# HARE_-_Master_Schematic_v1_0.net
KiCad netlist of a schematic drawn in EAGLE
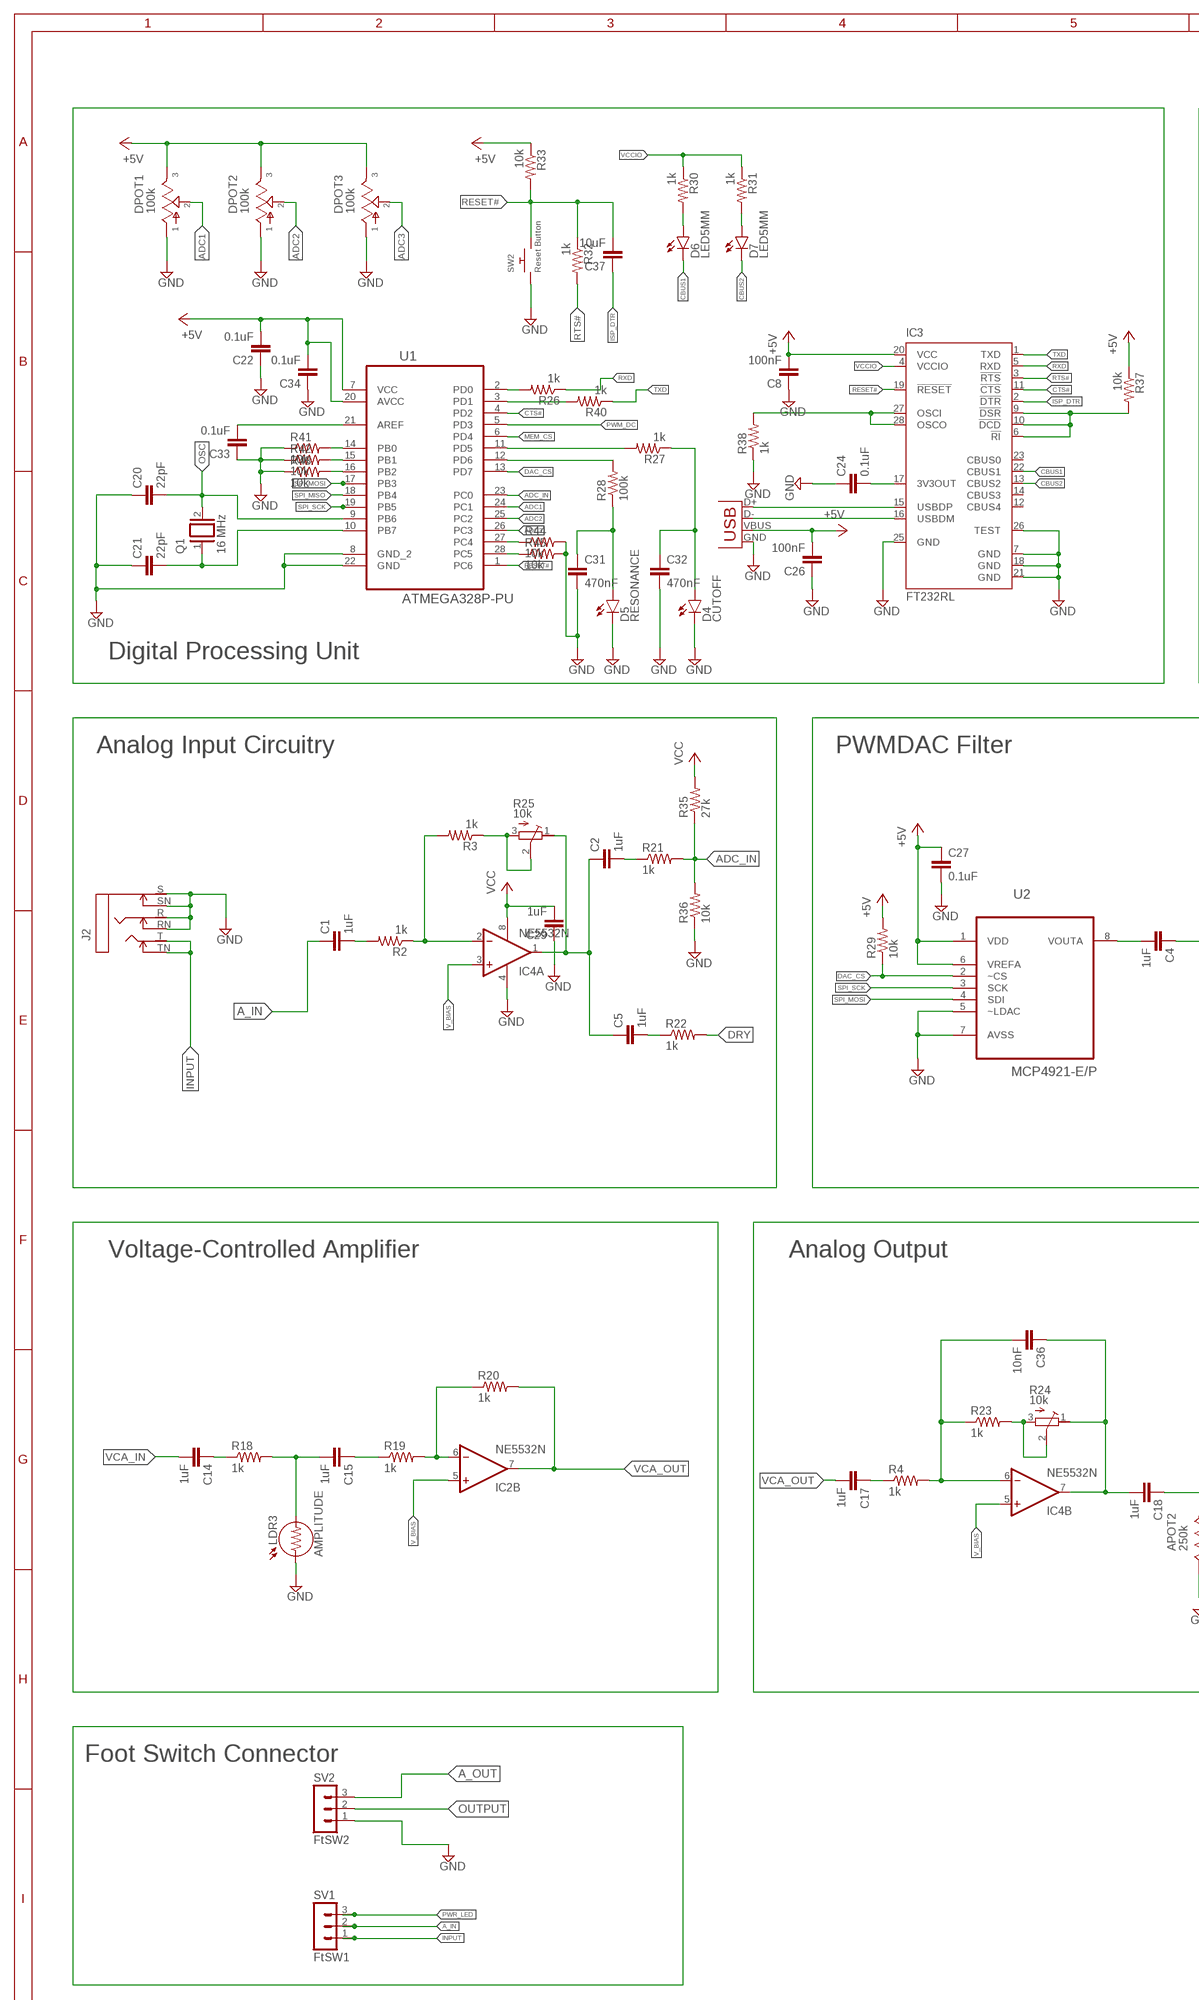
[diagram p0: schematic, sheet 1, part 1 of 2]
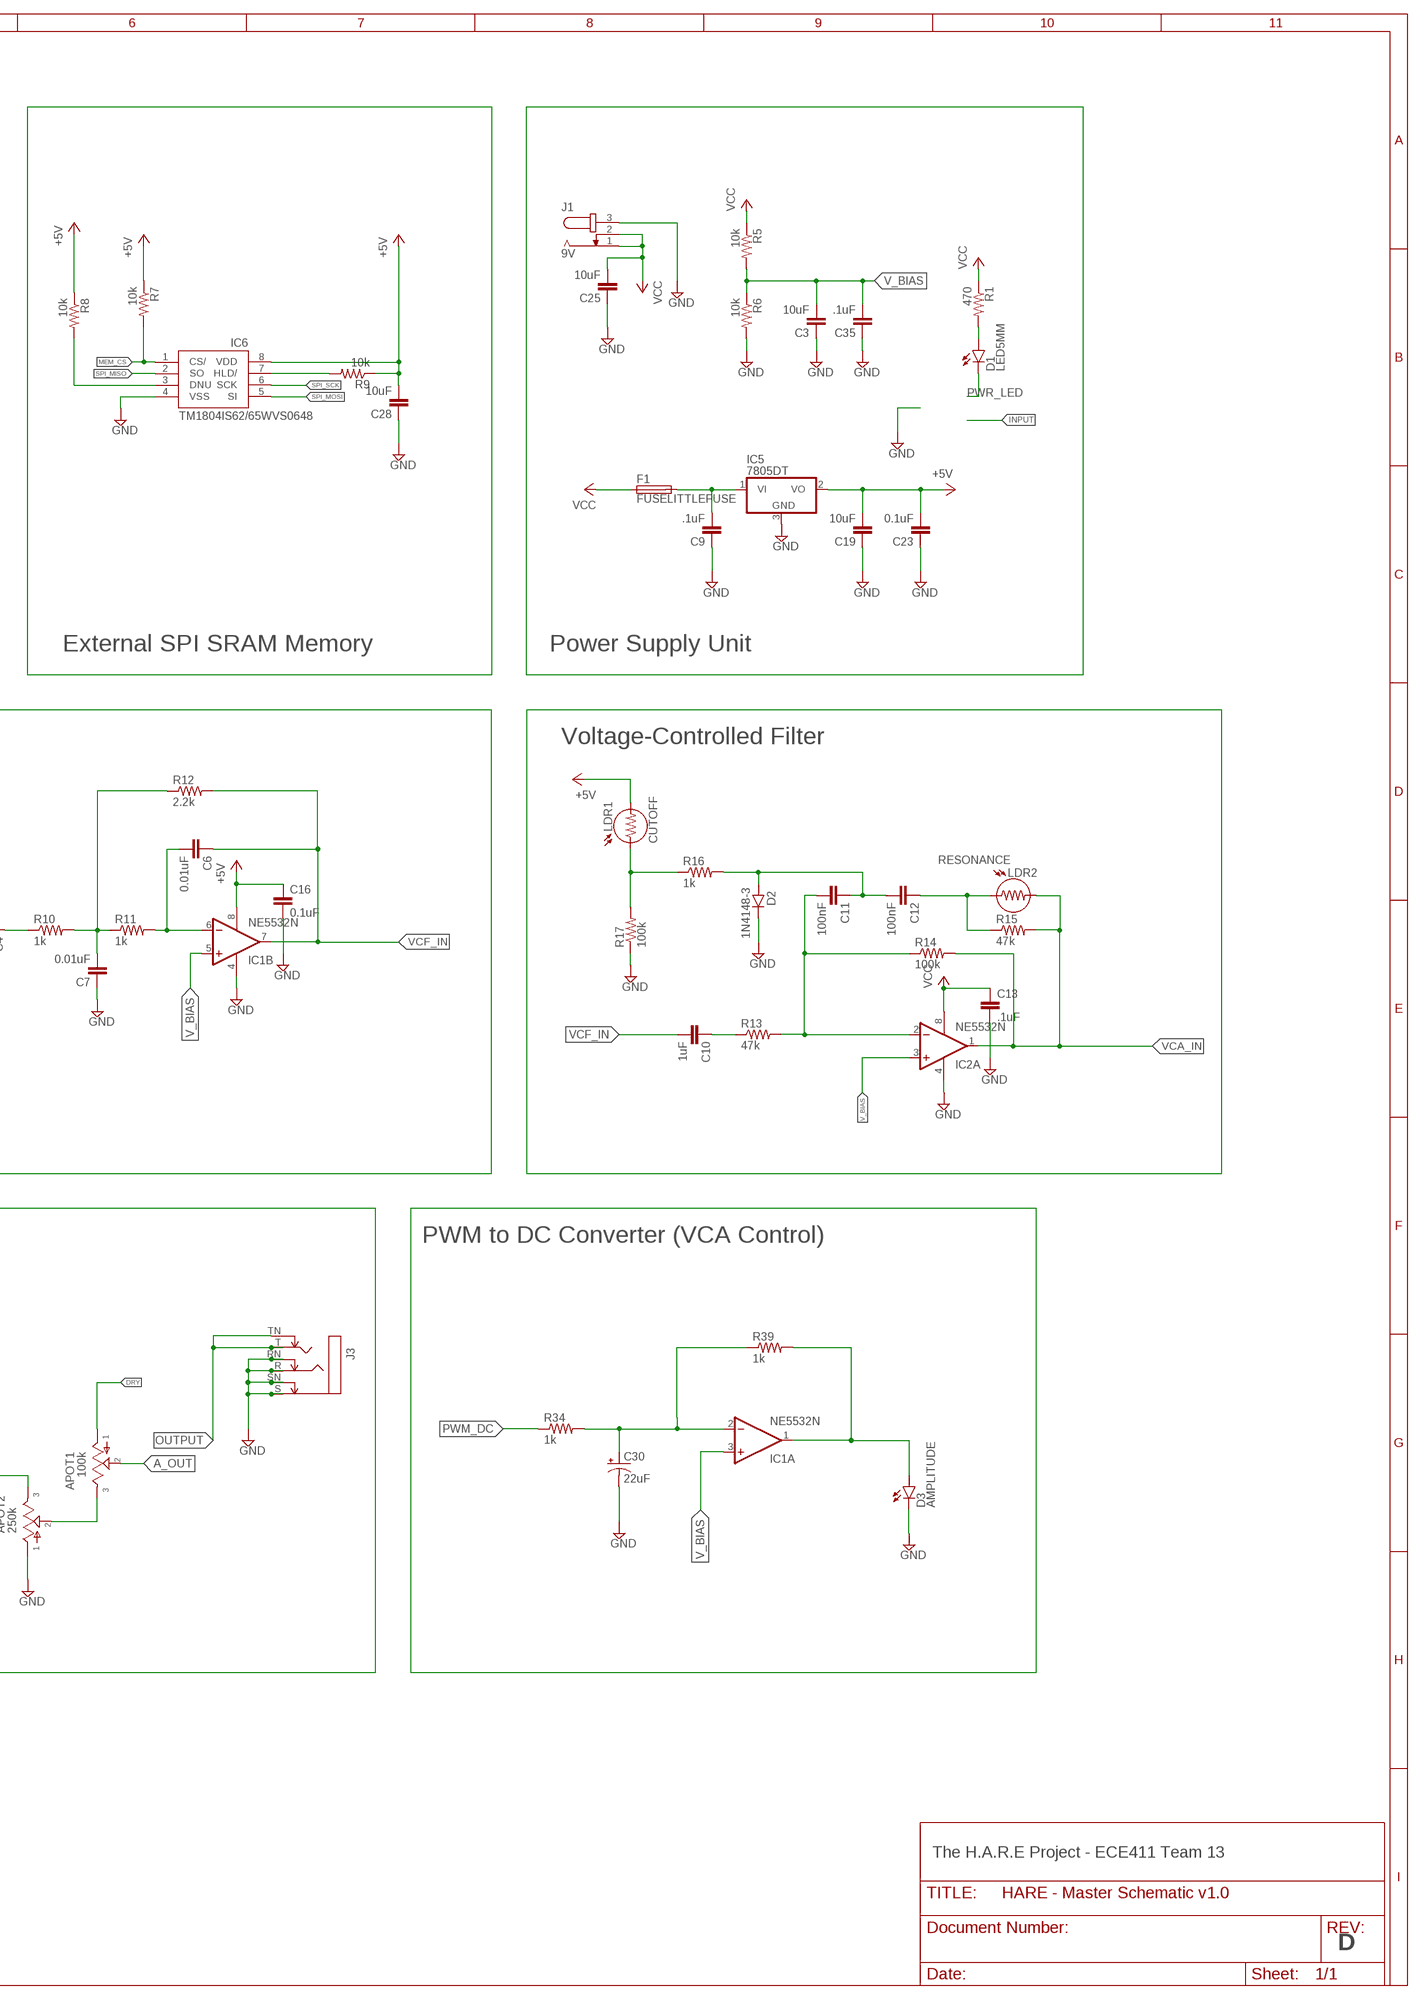
[diagram p1: schematic, sheet 1, part 2 of 2]

(export (version "E")
  (design (tool "Eeschema 10.0.6"))
  (components
    (comp (ref "APOT1")
      (value "100k")
      (footprint "eagle-import:16MM-SQUARE")
      (libsource (lib "eagle-import") (part "POTS"))
    )
    (comp (ref "APOT2")
      (value "250k")
      (footprint "eagle-import:16MM-SQUARE")
      (libsource (lib "eagle-import") (part "POTS"))
    )
    (comp (ref "C1")
      (value "1uF")
      (footprint "eagle-import:C0805K")
      (libsource (lib "eagle-import") (part "C-EUC0805K"))
    )
    (comp (ref "C2")
      (value "1uF")
      (footprint "eagle-import:C0805K")
      (libsource (lib "eagle-import") (part "C-EUC0805K"))
    )
    (comp (ref "C3")
      (value "10uF")
      (footprint "eagle-import:C0805K")
      (libsource (lib "eagle-import") (part "C-EUC0805K"))
    )
    (comp (ref "C4")
      (value "1uF")
      (footprint "eagle-import:C0805K")
      (libsource (lib "eagle-import") (part "C-EUC0805K"))
    )
    (comp (ref "C5")
      (value "1uF")
      (footprint "eagle-import:C0805K")
      (libsource (lib "eagle-import") (part "C-EUC0805K"))
    )
    (comp (ref "C6")
      (value "0.01uF")
      (footprint "eagle-import:C0805K")
      (libsource (lib "eagle-import") (part "C-EUC0805K"))
    )
    (comp (ref "C7")
      (value "0.01uF")
      (footprint "eagle-import:C0805K")
      (libsource (lib "eagle-import") (part "C-EUC0805K"))
    )
    (comp (ref "C8")
      (value "100nF")
      (footprint "eagle-import:C0805K")
      (libsource (lib "eagle-import") (part "C-EUC0805K"))
    )
    (comp (ref "C9")
      (value ".1uF")
      (footprint "eagle-import:C0805K")
      (libsource (lib "eagle-import") (part "C-EUC0805K"))
    )
    (comp (ref "C10")
      (value "1uF")
      (footprint "eagle-import:C0805K")
      (libsource (lib "eagle-import") (part "C-EUC0805K"))
    )
    (comp (ref "C11")
      (value "100nF")
      (footprint "eagle-import:C0805K")
      (libsource (lib "eagle-import") (part "C-EUC0805K"))
    )
    (comp (ref "C12")
      (value "100nF")
      (footprint "eagle-import:C0805K")
      (libsource (lib "eagle-import") (part "C-EUC0805K"))
    )
    (comp (ref "C13")
      (value ".1uF")
      (footprint "eagle-import:C0805K")
      (libsource (lib "eagle-import") (part "C-EUC0805K"))
    )
    (comp (ref "C14")
      (value "1uF")
      (footprint "eagle-import:C0805K")
      (libsource (lib "eagle-import") (part "C-EUC0805K"))
    )
    (comp (ref "C15")
      (value "1uF")
      (footprint "eagle-import:C0805K")
      (libsource (lib "eagle-import") (part "C-EUC0805K"))
    )
    (comp (ref "C16")
      (value "0.1uF")
      (footprint "eagle-import:C0805K")
      (libsource (lib "eagle-import") (part "C-EUC0805K"))
    )
    (comp (ref "C17")
      (value "1uF")
      (footprint "eagle-import:C0805K")
      (libsource (lib "eagle-import") (part "C-EUC0805K"))
    )
    (comp (ref "C18")
      (value "1uF")
      (footprint "eagle-import:C0805K")
      (libsource (lib "eagle-import") (part "C-EUC0805K"))
    )
    (comp (ref "C19")
      (value "10uF")
      (footprint "eagle-import:C0805K")
      (libsource (lib "eagle-import") (part "C-EUC0805K"))
    )
    (comp (ref "C20")
      (value "22pF")
      (footprint "eagle-import:C0805K")
      (libsource (lib "eagle-import") (part "C-EUC0805K"))
    )
    (comp (ref "C21")
      (value "22pF")
      (footprint "eagle-import:C0805K")
      (libsource (lib "eagle-import") (part "C-EUC0805K"))
    )
    (comp (ref "C22")
      (value "0.1uF")
      (footprint "eagle-import:C0805K")
      (libsource (lib "eagle-import") (part "C-EUC0805K"))
    )
    (comp (ref "C23")
      (value "0.1uF")
      (footprint "eagle-import:C0805K")
      (libsource (lib "eagle-import") (part "C-EUC0805K"))
    )
    (comp (ref "C24")
      (value "0.1uF")
      (footprint "eagle-import:C0805K")
      (libsource (lib "eagle-import") (part "C-EUC0805K"))
    )
    (comp (ref "C25")
      (value "10uF")
      (footprint "eagle-import:C0805K")
      (libsource (lib "eagle-import") (part "C-EUC0805K"))
    )
    (comp (ref "C26")
      (value "100nF")
      (footprint "eagle-import:C0805K")
      (libsource (lib "eagle-import") (part "C-EUC0805K"))
    )
    (comp (ref "C27")
      (value "0.1uF")
      (footprint "eagle-import:C0805K")
      (libsource (lib "eagle-import") (part "C-EUC0805K"))
    )
    (comp (ref "C28")
      (value "10uF")
      (footprint "eagle-import:C0805K")
      (libsource (lib "eagle-import") (part "C-EUC0805K"))
    )
    (comp (ref "C29")
      (value "1uF")
      (footprint "eagle-import:C0805K")
      (libsource (lib "eagle-import") (part "C-EUC0805K"))
    )
    (comp (ref "C30")
      (value "22uF")
      (footprint "eagle-import:050_020_1")
      (libsource (lib "eagle-import") (part "0501"))
    )
    (comp (ref "C31")
      (value "470nF")
      (footprint "eagle-import:072X035")
      (libsource (lib "eagle-import") (part "072X0352"))
    )
    (comp (ref "C32")
      (value "470nF")
      (footprint "eagle-import:072X035")
      (libsource (lib "eagle-import") (part "072X0352"))
    )
    (comp (ref "C33")
      (value "0.1uF")
      (footprint "eagle-import:C0805K")
      (libsource (lib "eagle-import") (part "C-EUC0805K"))
    )
    (comp (ref "C34")
      (value "0.1uF")
      (footprint "eagle-import:C0805K")
      (libsource (lib "eagle-import") (part "C-EUC0805K"))
    )
    (comp (ref "C35")
      (value ".1uF")
      (footprint "eagle-import:C0805K")
      (libsource (lib "eagle-import") (part "C-EUC0805K"))
    )
    (comp (ref "C36")
      (value "10nF")
      (footprint "eagle-import:C0805K")
      (libsource (lib "eagle-import") (part "C-EUC0805K"))
    )
    (comp (ref "C37")
      (value "10uF")
      (footprint "eagle-import:C0805K")
      (libsource (lib "eagle-import") (part "C-EUC0805K"))
    )
    (comp (ref "D1")
      (value "LED5MM")
      (footprint "eagle-import:LED5MM")
      (libsource (lib "eagle-import") (part "LED5MM"))
    )
    (comp (ref "D2")
      (value "1N4148-3")
      (footprint "eagle-import:DO35-3")
      (libsource (lib "eagle-import") (part "1N4148-3"))
    )
    (comp (ref "D3")
      (value "AMPLITUDE")
      (footprint "eagle-import:LED5MM")
      (libsource (lib "eagle-import") (part "LED5MM"))
    )
    (comp (ref "D4")
      (value "CUTOFF")
      (footprint "eagle-import:LED5MM")
      (libsource (lib "eagle-import") (part "LED5MM"))
    )
    (comp (ref "D5")
      (value "RESONANCE")
      (footprint "eagle-import:LED5MM")
      (libsource (lib "eagle-import") (part "LED5MM"))
    )
    (comp (ref "D6")
      (value "LED5MM")
      (footprint "eagle-import:LED5MM")
      (libsource (lib "eagle-import") (part "LED5MM"))
    )
    (comp (ref "D7")
      (value "LED5MM")
      (footprint "eagle-import:LED5MM")
      (libsource (lib "eagle-import") (part "LED5MM"))
    )
    (comp (ref "DPOT1")
      (value "100k")
      (footprint "eagle-import:16MM-SQUARE")
      (libsource (lib "eagle-import") (part "POTS"))
    )
    (comp (ref "DPOT2")
      (value "100k")
      (footprint "eagle-import:16MM-SQUARE")
      (libsource (lib "eagle-import") (part "POTS"))
    )
    (comp (ref "DPOT3")
      (value "100k")
      (footprint "eagle-import:16MM-SQUARE")
      (libsource (lib "eagle-import") (part "POTS"))
    )
    (comp (ref "F1")
      (value "FUSELITTLEFUSE")
      (footprint "eagle-import:LITTLEFUSE")
      (libsource (lib "eagle-import") (part "FUSELITTLEFUSE"))
    )
    (comp (ref "IC1")
      (value "NE5532N")
      (footprint "eagle-import:DIL08")
      (libsource (lib "eagle-import") (part "NE5532N"))
    )
    (comp (ref "IC2")
      (value "NE5532N")
      (footprint "eagle-import:DIL08")
      (libsource (lib "eagle-import") (part "NE5532N"))
    )
    (comp (ref "IC3")
      (value "FT232RL")
      (footprint "eagle-import:SSOP28")
      (libsource (lib "eagle-import") (part "FT232RL"))
    )
    (comp (ref "IC4")
      (value "NE5532N")
      (footprint "eagle-import:DIL08")
      (libsource (lib "eagle-import") (part "NE5532N"))
    )
    (comp (ref "IC5")
      (value "7805DT")
      (footprint "eagle-import:TO252")
      (libsource (lib "eagle-import") (part "78DT05"))
    )
    (comp (ref "IC6")
      (value "TM1804IS62/65WVS0648")
      (footprint "eagle-import:SO08")
      (libsource (lib "eagle-import") (part "TM1804IS62/65WVS0648"))
    )
    (comp (ref "J1")
      (value "9V")
      (footprint "eagle-import:SPC4078")
      (libsource (lib "eagle-import") (part "JACK-PLUG1"))
    )
    (comp (ref "J2")
      (value "STEREOSW")
      (footprint "eagle-import:NMJ6HCD2")
      (libsource (lib "eagle-import") (part "STEREOSW"))
    )
    (comp (ref "J3")
      (value "STEREOSW")
      (footprint "eagle-import:NMJ6HCD2")
      (libsource (lib "eagle-import") (part "STEREOSW"))
    )
    (comp (ref "LDR1")
      (value "CUTOFF")
      (footprint "eagle-import:LDR338-54C")
      (libsource (lib "eagle-import") (part "LDR5MM"))
    )
    (comp (ref "LDR2")
      (value "RESONANCE")
      (footprint "eagle-import:LDR338-54C")
      (libsource (lib "eagle-import") (part "LDR5MM"))
    )
    (comp (ref "LDR3")
      (value "AMPLITUDE")
      (footprint "eagle-import:LDR338-54C")
      (libsource (lib "eagle-import") (part "LDR5MM"))
    )
    (comp (ref "Q1")
      (value "16 MHz")
      (footprint "eagle-import:QS")
      (libsource (lib "eagle-import") (part "XTAL/S"))
    )
    (comp (ref "R1")
      (value "470")
      (footprint "eagle-import:M0805")
      (libsource (lib "eagle-import") (part "R-US_M0805"))
    )
    (comp (ref "R2")
      (value "1k")
      (footprint "eagle-import:R0805")
      (libsource (lib "eagle-import") (part "resistor_348_R-US_R0805"))
    )
    (comp (ref "R3")
      (value "1k")
      (footprint "eagle-import:R0805")
      (libsource (lib "eagle-import") (part "resistor_348_R-US_R0805"))
    )
    (comp (ref "R4")
      (value "1k")
      (footprint "eagle-import:R0805")
      (libsource (lib "eagle-import") (part "resistor_348_R-US_R0805"))
    )
    (comp (ref "R5")
      (value "10k")
      (footprint "eagle-import:M0805")
      (libsource (lib "eagle-import") (part "R-US_M0805"))
    )
    (comp (ref "R6")
      (value "10k")
      (footprint "eagle-import:M0805")
      (libsource (lib "eagle-import") (part "R-US_M0805"))
    )
    (comp (ref "R7")
      (value "10k")
      (footprint "eagle-import:M0805")
      (libsource (lib "eagle-import") (part "R-US_M0805"))
    )
    (comp (ref "R8")
      (value "10k")
      (footprint "eagle-import:M0805")
      (libsource (lib "eagle-import") (part "R-US_M0805"))
    )
    (comp (ref "R9")
      (value "10k")
      (footprint "eagle-import:M0805")
      (libsource (lib "eagle-import") (part "R-US_M0805"))
    )
    (comp (ref "R10")
      (value "1k")
      (footprint "eagle-import:R0805")
      (libsource (lib "eagle-import") (part "resistor_348_R-US_R0805"))
    )
    (comp (ref "R11")
      (value "1k")
      (footprint "eagle-import:R0805")
      (libsource (lib "eagle-import") (part "resistor_348_R-US_R0805"))
    )
    (comp (ref "R12")
      (value "2.2k")
      (footprint "eagle-import:R0805")
      (libsource (lib "eagle-import") (part "resistor_348_R-US_R0805"))
    )
    (comp (ref "R13")
      (value "47k")
      (footprint "eagle-import:R0805")
      (libsource (lib "eagle-import") (part "resistor_348_R-US_R0805"))
    )
    (comp (ref "R14")
      (value "100k")
      (footprint "eagle-import:R0805")
      (libsource (lib "eagle-import") (part "resistor_348_R-US_R0805"))
    )
    (comp (ref "R15")
      (value "47k")
      (footprint "eagle-import:R0805")
      (libsource (lib "eagle-import") (part "resistor_348_R-US_R0805"))
    )
    (comp (ref "R16")
      (value "1k")
      (footprint "eagle-import:R0805")
      (libsource (lib "eagle-import") (part "resistor_348_R-US_R0805"))
    )
    (comp (ref "R17")
      (value "100k")
      (footprint "eagle-import:R0805")
      (libsource (lib "eagle-import") (part "resistor_348_R-US_R0805"))
    )
    (comp (ref "R18")
      (value "1k")
      (footprint "eagle-import:R0805")
      (libsource (lib "eagle-import") (part "resistor_348_R-US_R0805"))
    )
    (comp (ref "R19")
      (value "1k")
      (footprint "eagle-import:R0805")
      (libsource (lib "eagle-import") (part "resistor_348_R-US_R0805"))
    )
    (comp (ref "R20")
      (value "1k")
      (footprint "eagle-import:R0805")
      (libsource (lib "eagle-import") (part "resistor_348_R-US_R0805"))
    )
    (comp (ref "R21")
      (value "1k")
      (footprint "eagle-import:R0805")
      (libsource (lib "eagle-import") (part "resistor_348_R-US_R0805"))
    )
    (comp (ref "R22")
      (value "1k")
      (footprint "eagle-import:R0805")
      (libsource (lib "eagle-import") (part "resistor_348_R-US_R0805"))
    )
    (comp (ref "R23")
      (value "1k")
      (footprint "eagle-import:R0805")
      (libsource (lib "eagle-import") (part "resistor_348_R-US_R0805"))
    )
    (comp (ref "R24")
      (value "10k")
      (footprint "eagle-import:RTRIM3314G")
      (libsource (lib "eagle-import") (part "R-TRIMM3314G"))
    )
    (comp (ref "R25")
      (value "10k")
      (footprint "eagle-import:RTRIM3314G")
      (libsource (lib "eagle-import") (part "R-TRIMM3314G"))
    )
    (comp (ref "R26")
      (value "1k")
      (footprint "eagle-import:R0805")
      (libsource (lib "eagle-import") (part "resistor_348_R-US_R0805"))
    )
    (comp (ref "R27")
      (value "1k")
      (footprint "eagle-import:R0805")
      (libsource (lib "eagle-import") (part "resistor_348_R-US_R0805"))
    )
    (comp (ref "R28")
      (value "100k")
      (footprint "eagle-import:R0805")
      (libsource (lib "eagle-import") (part "resistor_348_R-US_R0805"))
    )
    (comp (ref "R29")
      (value "10k")
      (footprint "eagle-import:R0805")
      (libsource (lib "eagle-import") (part "resistor_348_R-US_R0805"))
    )
    (comp (ref "R30")
      (value "1k")
      (footprint "eagle-import:R0805")
      (libsource (lib "eagle-import") (part "resistor_348_R-US_R0805"))
    )
    (comp (ref "R31")
      (value "1k")
      (footprint "eagle-import:R0805")
      (libsource (lib "eagle-import") (part "resistor_348_R-US_R0805"))
    )
    (comp (ref "R32")
      (value "1k")
      (footprint "eagle-import:R0805")
      (libsource (lib "eagle-import") (part "resistor_348_R-US_R0805"))
    )
    (comp (ref "R33")
      (value "10k")
      (footprint "eagle-import:R0805")
      (libsource (lib "eagle-import") (part "resistor_348_R-US_R0805"))
    )
    (comp (ref "R34")
      (value "1k")
      (footprint "eagle-import:R0805")
      (libsource (lib "eagle-import") (part "resistor_348_R-US_R0805"))
    )
    (comp (ref "R35")
      (value "27k")
      (footprint "eagle-import:R0805")
      (libsource (lib "eagle-import") (part "resistor_348_R-US_R0805"))
    )
    (comp (ref "R36")
      (value "10k")
      (footprint "eagle-import:R0805")
      (libsource (lib "eagle-import") (part "resistor_348_R-US_R0805"))
    )
    (comp (ref "R37")
      (value "10k")
      (footprint "eagle-import:R0805")
      (libsource (lib "eagle-import") (part "resistor_348_R-US_R0805"))
    )
    (comp (ref "R38")
      (value "1k")
      (footprint "eagle-import:R0805")
      (libsource (lib "eagle-import") (part "resistor_348_R-US_R0805"))
    )
    (comp (ref "R39")
      (value "1k")
      (footprint "eagle-import:R0805")
      (libsource (lib "eagle-import") (part "resistor_348_R-US_R0805"))
    )
    (comp (ref "R40")
      (value "1k")
      (footprint "eagle-import:R0805")
      (libsource (lib "eagle-import") (part "resistor_348_R-US_R0805"))
    )
    (comp (ref "R41")
      (value "10k")
      (footprint "eagle-import:R0805")
      (libsource (lib "eagle-import") (part "resistor_348_R-US_R0805"))
    )
    (comp (ref "R42")
      (value "10k")
      (footprint "eagle-import:R0805")
      (libsource (lib "eagle-import") (part "resistor_348_R-US_R0805"))
    )
    (comp (ref "R43")
      (value "10k")
      (footprint "eagle-import:R0805")
      (libsource (lib "eagle-import") (part "resistor_348_R-US_R0805"))
    )
    (comp (ref "R44")
      (value "10k")
      (footprint "eagle-import:R0805")
      (libsource (lib "eagle-import") (part "resistor_348_R-US_R0805"))
    )
    (comp (ref "R45")
      (value "10k")
      (footprint "eagle-import:R0805")
      (libsource (lib "eagle-import") (part "resistor_348_R-US_R0805"))
    )
    (comp (ref "SV1")
      (value "FtSW1")
      (footprint "eagle-import:MA03-1")
      (libsource (lib "eagle-import") (part "MA03-1"))
    )
    (comp (ref "SV2")
      (value "FtSW2")
      (footprint "eagle-import:MA03-1")
      (libsource (lib "eagle-import") (part "MA03-1"))
    )
    (comp (ref "SW2")
      (value "Reset Button")
      (footprint "eagle-import:PUSHBUTTON_SMD_SJ")
      (libsource (lib "eagle-import") (part "SWITCH_PUSHBUTTONSOFTTOUCHSMD_SJ"))
    )
    (comp (ref "U1")
      (value "ATMEGA328P-PU")
      (footprint "eagle-import:DIP254P762X457-28")
      (libsource (lib "eagle-import") (part "ATMEGA328P-PU"))
    )
    (comp (ref "U2")
      (value "MCP4921-E/P")
      (footprint "eagle-import:DIP254P762X432-8")
      (fields (field (name "MF") "Microchip"))
      (libsource (lib "eagle-import") (part "MCP4921-E/P"))
    )
    (comp (ref "X2")
      (value "USB-B-H")
      (footprint "eagle-import:USB-B-H")
      (libsource (lib "eagle-import") (part "USB-B-H"))
    )
  )
  (nets
    (net (code "1") (name "+5V") (class "Default")
      (node (ref "C16") (pin "1") (pinfunction "1_1") (pintype "passive"))
      (node (ref "C19") (pin "2") (pinfunction "2_2") (pintype "passive"))
      (node (ref "C22") (pin "2") (pinfunction "2_2") (pintype "passive"))
      (node (ref "C23") (pin "2") (pinfunction "2_2") (pintype "passive"))
      (node (ref "C26") (pin "2") (pinfunction "2_2") (pintype "passive"))
      (node (ref "C27") (pin "1") (pinfunction "1_1") (pintype "passive"))
      (node (ref "C28") (pin "2") (pinfunction "2_2") (pintype "passive"))
      (node (ref "C34") (pin "2") (pinfunction "2_2") (pintype "passive"))
      (node (ref "C8") (pin "2") (pinfunction "2_2") (pintype "passive"))
      (node (ref "DPOT1") (pin "3") (pinfunction "3_3") (pintype "passive"))
      (node (ref "DPOT2") (pin "3") (pinfunction "3_3") (pintype "passive"))
      (node (ref "DPOT3") (pin "3") (pinfunction "3_3") (pintype "passive"))
      (node (ref "IC1") (pin "8") (pinfunction "V+_8") (pintype "power_in"))
      (node (ref "IC3") (pin "20") (pinfunction "VCC_20") (pintype "power_in"))
      (node (ref "IC5") (pin "2") (pinfunction "VO_2") (pintype "passive"))
      (node (ref "IC6") (pin "8") (pinfunction "VDD_8") (pintype "power_in"))
      (node (ref "LDR1") (pin "2") (pinfunction "2_2") (pintype "passive"))
      (node (ref "R29") (pin "2") (pinfunction "2_2") (pintype "passive"))
      (node (ref "R33") (pin "1") (pinfunction "1_1") (pintype "passive"))
      (node (ref "R37") (pin "1") (pinfunction "1_1") (pintype "passive"))
      (node (ref "R7") (pin "1") (pinfunction "1_1") (pintype "passive"))
      (node (ref "R8") (pin "1") (pinfunction "1_1") (pintype "passive"))
      (node (ref "R9") (pin "1") (pinfunction "1_1") (pintype "passive"))
      (node (ref "U1") (pin "20") (pinfunction "AVCC_20") (pintype "power_in"))
      (node (ref "U1") (pin "7") (pinfunction "VCC_7") (pintype "power_in"))
      (node (ref "U2") (pin "1") (pinfunction "VDD_1") (pintype "power_in"))
      (node (ref "U2") (pin "6") (pinfunction "VREFA_6") (pintype "input"))
      (node (ref "X2") (pin "VBUS") (pinfunction "VBUS_VBUS") (pintype "bidirectional"))
    )
    (net (code "2") (name "ADC1") (class "Default")
      (node (ref "DPOT1") (pin "2") (pinfunction "2_2") (pintype "passive"))
      (node (ref "U1") (pin "24") (pinfunction "PC1_24") (pintype "bidirectional"))
    )
    (net (code "3") (name "ADC2") (class "Default")
      (node (ref "DPOT2") (pin "2") (pinfunction "2_2") (pintype "passive"))
      (node (ref "U1") (pin "25") (pinfunction "PC2_25") (pintype "bidirectional"))
    )
    (net (code "4") (name "ADC3") (class "Default")
      (node (ref "DPOT3") (pin "2") (pinfunction "2_2") (pintype "passive"))
      (node (ref "U1") (pin "26") (pinfunction "PC3_26") (pintype "bidirectional"))
    )
    (net (code "5") (name "ADC_IN") (class "Default")
      (node (ref "R21") (pin "2") (pinfunction "2_2") (pintype "passive"))
      (node (ref "R35") (pin "1") (pinfunction "1_1") (pintype "passive"))
      (node (ref "R36") (pin "2") (pinfunction "2_2") (pintype "passive"))
      (node (ref "U1") (pin "23") (pinfunction "PC0_23") (pintype "bidirectional"))
    )
    (net (code "6") (name "A_IN") (class "Default")
      (node (ref "C1") (pin "1") (pinfunction "1_1") (pintype "passive"))
      (node (ref "SV1") (pin "2") (pinfunction "2_2") (pintype "passive"))
    )
    (net (code "7") (name "A_OUT") (class "Default")
      (node (ref "APOT1") (pin "2") (pinfunction "2_2") (pintype "passive"))
      (node (ref "SV2") (pin "3") (pinfunction "3_3") (pintype "passive"))
    )
    (net (code "8") (name "CBUS1") (class "Default")
      (node (ref "D6") (pin "K") (pinfunction "C_K") (pintype "passive"))
      (node (ref "IC3") (pin "22") (pinfunction "CBUS1_22") (pintype "bidirectional"))
    )
    (net (code "9") (name "CBUS2") (class "Default")
      (node (ref "D7") (pin "K") (pinfunction "C_K") (pintype "passive"))
      (node (ref "IC3") (pin "13") (pinfunction "CBUS2_13") (pintype "bidirectional"))
    )
    (net (code "10") (name "CTS#") (class "Default")
      (node (ref "IC3") (pin "11") (pinfunction "~{CTS}_11") (pintype "input"))
      (node (ref "U1") (pin "4") (pinfunction "PD2_4") (pintype "bidirectional"))
    )
    (net (code "11") (name "DAC_CS") (class "Default")
      (node (ref "R29") (pin "1") (pinfunction "1_1") (pintype "passive"))
      (node (ref "U1") (pin "13") (pinfunction "PD7_13") (pintype "bidirectional"))
      (node (ref "U2") (pin "2") (pinfunction "~{CS}_2") (pintype "input"))
    )
    (net (code "12") (name "DRY") (class "Default")
      (node (ref "APOT1") (pin "1") (pinfunction "1_1") (pintype "passive"))
      (node (ref "R22") (pin "2") (pinfunction "2_2") (pintype "passive"))
    )
    (net (code "13") (name "GND") (class "Default")
      (node (ref "APOT2") (pin "1") (pinfunction "1_1") (pintype "passive"))
      (node (ref "C13") (pin "2") (pinfunction "2_2") (pintype "passive"))
      (node (ref "C16") (pin "2") (pinfunction "2_2") (pintype "passive"))
      (node (ref "C19") (pin "1") (pinfunction "1_1") (pintype "passive"))
      (node (ref "C20") (pin "1") (pinfunction "1_1") (pintype "passive"))
      (node (ref "C21") (pin "1") (pinfunction "1_1") (pintype "passive"))
      (node (ref "C22") (pin "1") (pinfunction "1_1") (pintype "passive"))
      (node (ref "C23") (pin "1") (pinfunction "1_1") (pintype "passive"))
      (node (ref "C24") (pin "1") (pinfunction "1_1") (pintype "passive"))
      (node (ref "C25") (pin "1") (pinfunction "1_1") (pintype "passive"))
      (node (ref "C26") (pin "1") (pinfunction "1_1") (pintype "passive"))
      (node (ref "C27") (pin "2") (pinfunction "2_2") (pintype "passive"))
      (node (ref "C28") (pin "1") (pinfunction "1_1") (pintype "passive"))
      (node (ref "C29") (pin "1") (pinfunction "1_1") (pintype "passive"))
      (node (ref "C3") (pin "1") (pinfunction "1_1") (pintype "passive"))
      (node (ref "C30") (pin "-") (pinfunction "-_-") (pintype "passive"))
      (node (ref "C31") (pin "2") (pinfunction "2_2") (pintype "passive"))
      (node (ref "C32") (pin "2") (pinfunction "2_2") (pintype "passive"))
      (node (ref "C33") (pin "1") (pinfunction "1_1") (pintype "passive"))
      (node (ref "C34") (pin "1") (pinfunction "1_1") (pintype "passive"))
      (node (ref "C35") (pin "1") (pinfunction "1_1") (pintype "passive"))
      (node (ref "C7") (pin "1") (pinfunction "1_1") (pintype "passive"))
      (node (ref "C8") (pin "1") (pinfunction "1_1") (pintype "passive"))
      (node (ref "C9") (pin "1") (pinfunction "1_1") (pintype "passive"))
      (node (ref "D2") (pin "C") (pinfunction "C_C") (pintype "passive"))
      (node (ref "D3") (pin "K") (pinfunction "C_K") (pintype "passive"))
      (node (ref "D4") (pin "K") (pinfunction "C_K") (pintype "passive"))
      (node (ref "D5") (pin "K") (pinfunction "C_K") (pintype "passive"))
      (node (ref "DPOT1") (pin "1") (pinfunction "1_1") (pintype "passive"))
      (node (ref "DPOT2") (pin "1") (pinfunction "1_1") (pintype "passive"))
      (node (ref "DPOT3") (pin "1") (pinfunction "1_1") (pintype "passive"))
      (node (ref "IC1") (pin "4") (pinfunction "V-_4") (pintype "power_in"))
      (node (ref "IC2") (pin "4") (pinfunction "V-_4") (pintype "power_in"))
      (node (ref "IC3") (pin "18") (pinfunction "GND_18") (pintype "power_in"))
      (node (ref "IC3") (pin "21") (pinfunction "GND_21") (pintype "power_in"))
      (node (ref "IC3") (pin "25") (pinfunction "GND_25") (pintype "power_in"))
      (node (ref "IC3") (pin "26") (pinfunction "TEST_26") (pintype "input"))
      (node (ref "IC3") (pin "7") (pinfunction "GND_7") (pintype "power_in"))
      (node (ref "IC4") (pin "4") (pinfunction "V-_4") (pintype "power_in"))
      (node (ref "IC5") (pin "3") (pinfunction "GND_3") (pintype "passive"))
      (node (ref "IC6") (pin "4") (pinfunction "VSS_4") (pintype "power_in"))
      (node (ref "J1") (pin "3") (pinfunction "3_3") (pintype "passive"))
      (node (ref "J2") (pin "R") (pinfunction "R_R") (pintype "passive"))
      (node (ref "J2") (pin "RN") (pinfunction "RN_RN") (pintype "passive"))
      (node (ref "J2") (pin "S") (pinfunction "S_S") (pintype "passive"))
      (node (ref "J2") (pin "SN") (pinfunction "SN_SN") (pintype "passive"))
      (node (ref "J3") (pin "R") (pinfunction "R_R") (pintype "passive"))
      (node (ref "J3") (pin "RN") (pinfunction "RN_RN") (pintype "passive"))
      (node (ref "J3") (pin "S") (pinfunction "S_S") (pintype "passive"))
      (node (ref "J3") (pin "SN") (pinfunction "SN_SN") (pintype "passive"))
      (node (ref "LDR3") (pin "1") (pinfunction "1_1") (pintype "passive"))
      (node (ref "R17") (pin "1") (pinfunction "1_1") (pintype "passive"))
      (node (ref "R36") (pin "1") (pinfunction "1_1") (pintype "passive"))
      (node (ref "R38") (pin "1") (pinfunction "1_1") (pintype "passive"))
      (node (ref "R41") (pin "1") (pinfunction "1_1") (pintype "passive"))
      (node (ref "R42") (pin "1") (pinfunction "1_1") (pintype "passive"))
      (node (ref "R43") (pin "1") (pinfunction "1_1") (pintype "passive"))
      (node (ref "R44") (pin "2") (pinfunction "2_2") (pintype "passive"))
      (node (ref "R45") (pin "2") (pinfunction "2_2") (pintype "passive"))
      (node (ref "R6") (pin "2") (pinfunction "2_2") (pintype "passive"))
      (node (ref "SV2") (pin "1") (pinfunction "1_1") (pintype "passive"))
      (node (ref "SW2") (pin "P$1") (pinfunction "P$1_P$1") (pintype "passive"))
      (node (ref "U1") (pin "22") (pinfunction "GND_22") (pintype "passive"))
      (node (ref "U1") (pin "8") (pinfunction "GND_2_8") (pintype "passive"))
      (node (ref "U2") (pin "5") (pinfunction "~{LDAC}_5") (pintype "input"))
      (node (ref "U2") (pin "7") (pinfunction "AVSS_7") (pintype "passive"))
      (node (ref "X2") (pin "GND") (pinfunction "GND_GND") (pintype "bidirectional"))
    )
    (net (code "14") (name "INPUT") (class "Default")
      (node (ref "J2") (pin "T") (pinfunction "T_T") (pintype "passive"))
      (node (ref "J2") (pin "TN") (pinfunction "TN_TN") (pintype "passive"))
      (node (ref "SV1") (pin "1") (pinfunction "1_1") (pintype "passive"))
    )
    (net (code "15") (name "ISP_DTR") (class "Default")
      (node (ref "C37") (pin "1") (pinfunction "1_1") (pintype "passive"))
      (node (ref "IC3") (pin "2") (pinfunction "~{DTR}_2") (pintype "output"))
    )
    (net (code "16") (name "MEM_CS") (class "Default")
      (node (ref "IC6") (pin "1") (pinfunction "CS/_1") (pintype "input"))
      (node (ref "R7") (pin "2") (pinfunction "2_2") (pintype "passive"))
      (node (ref "U1") (pin "6") (pinfunction "PD4_6") (pintype "bidirectional"))
    )
    (net (code "17") (name "Net-(APOT1-Pad3)") (class "Default")
      (node (ref "APOT1") (pin "3") (pinfunction "3_3") (pintype "passive"))
      (node (ref "APOT2") (pin "2") (pinfunction "2_2") (pintype "passive"))
    )
    (net (code "18") (name "Net-(APOT2-Pad3)") (class "Default")
      (node (ref "APOT2") (pin "3") (pinfunction "3_3") (pintype "passive"))
      (node (ref "C18") (pin "1") (pinfunction "1_1") (pintype "passive"))
    )
    (net (code "19") (name "Net-(C1-Pad2)") (class "Default")
      (node (ref "C1") (pin "2") (pinfunction "2_2") (pintype "passive"))
      (node (ref "R2") (pin "2") (pinfunction "2_2") (pintype "passive"))
    )
    (net (code "20") (name "Net-(C2-Pad2)") (class "Default")
      (node (ref "C2") (pin "2") (pinfunction "2_2") (pintype "passive"))
      (node (ref "R21") (pin "1") (pinfunction "1_1") (pintype "passive"))
    )
    (net (code "21") (name "Net-(C4-Pad1)") (class "Default")
      (node (ref "C4") (pin "1") (pinfunction "1_1") (pintype "passive"))
      (node (ref "R10") (pin "1") (pinfunction "1_1") (pintype "passive"))
    )
    (net (code "22") (name "Net-(C5-Pad2)") (class "Default")
      (node (ref "C5") (pin "2") (pinfunction "2_2") (pintype "passive"))
      (node (ref "R22") (pin "1") (pinfunction "1_1") (pintype "passive"))
    )
    (net (code "23") (name "Net-(C7-Pad2)") (class "Default")
      (node (ref "C7") (pin "2") (pinfunction "2_2") (pintype "passive"))
      (node (ref "R10") (pin "2") (pinfunction "2_2") (pintype "passive"))
      (node (ref "R11") (pin "1") (pinfunction "1_1") (pintype "passive"))
      (node (ref "R12") (pin "1") (pinfunction "1_1") (pintype "passive"))
    )
    (net (code "24") (name "Net-(C10-Pad1)") (class "Default")
      (node (ref "C10") (pin "1") (pinfunction "1_1") (pintype "passive"))
      (node (ref "R13") (pin "1") (pinfunction "1_1") (pintype "passive"))
    )
    (net (code "25") (name "Net-(C11-Pad1)") (class "Default")
      (node (ref "C11") (pin "1") (pinfunction "1_1") (pintype "passive"))
      (node (ref "C12") (pin "2") (pinfunction "2_2") (pintype "passive"))
      (node (ref "D2") (pin "A") (pinfunction "A_A") (pintype "passive"))
      (node (ref "R16") (pin "2") (pinfunction "2_2") (pintype "passive"))
    )
    (net (code "26") (name "Net-(C12-Pad1)") (class "Default")
      (node (ref "C12") (pin "1") (pinfunction "1_1") (pintype "passive"))
      (node (ref "LDR2") (pin "1") (pinfunction "1_1") (pintype "passive"))
      (node (ref "R15") (pin "1") (pinfunction "1_1") (pintype "passive"))
    )
    (net (code "27") (name "Net-(C14-Pad1)") (class "Default")
      (node (ref "C14") (pin "1") (pinfunction "1_1") (pintype "passive"))
      (node (ref "R18") (pin "1") (pinfunction "1_1") (pintype "passive"))
    )
    (net (code "28") (name "Net-(C15-Pad1)") (class "Default")
      (node (ref "C15") (pin "1") (pinfunction "1_1") (pintype "passive"))
      (node (ref "R19") (pin "1") (pinfunction "1_1") (pintype "passive"))
    )
    (net (code "29") (name "Net-(C15-Pad2)") (class "Default")
      (node (ref "C15") (pin "2") (pinfunction "2_2") (pintype "passive"))
      (node (ref "LDR3") (pin "2") (pinfunction "2_2") (pintype "passive"))
      (node (ref "R18") (pin "2") (pinfunction "2_2") (pintype "passive"))
    )
    (net (code "30") (name "Net-(C17-Pad1)") (class "Default")
      (node (ref "C17") (pin "1") (pinfunction "1_1") (pintype "passive"))
      (node (ref "R4") (pin "1") (pinfunction "1_1") (pintype "passive"))
    )
    (net (code "31") (name "Net-(C31-Pad1)") (class "Default")
      (node (ref "C31") (pin "1") (pinfunction "1_1") (pintype "passive"))
      (node (ref "D5") (pin "A") (pinfunction "A_A") (pintype "passive"))
      (node (ref "R28") (pin "1") (pinfunction "1_1") (pintype "passive"))
    )
    (net (code "32") (name "Net-(C32-Pad1)") (class "Default")
      (node (ref "C32") (pin "1") (pinfunction "1_1") (pintype "passive"))
      (node (ref "D4") (pin "A") (pinfunction "A_A") (pintype "passive"))
      (node (ref "R27") (pin "1") (pinfunction "1_1") (pintype "passive"))
    )
    (net (code "33") (name "Net-(D1-PadA)") (class "Default")
      (node (ref "D1") (pin "A") (pinfunction "A_A") (pintype "passive"))
      (node (ref "R1") (pin "2") (pinfunction "2_2") (pintype "passive"))
    )
    (net (code "34") (name "Net-(D6-PadA)") (class "Default")
      (node (ref "D6") (pin "A") (pinfunction "A_A") (pintype "passive"))
      (node (ref "R30") (pin "2") (pinfunction "2_2") (pintype "passive"))
    )
    (net (code "35") (name "Net-(D7-PadA)") (class "Default")
      (node (ref "D7") (pin "A") (pinfunction "A_A") (pintype "passive"))
      (node (ref "R31") (pin "2") (pinfunction "2_2") (pintype "passive"))
    )
    (net (code "36") (name "Net-(IC1A--IN)") (class "Default")
      (node (ref "C30") (pin "+") (pinfunction "+_+") (pintype "passive"))
      (node (ref "IC1") (pin "2") (pinfunction "-IN_2") (pintype "input"))
      (node (ref "R34") (pin "2") (pinfunction "2_2") (pintype "passive"))
      (node (ref "R39") (pin "1") (pinfunction "1_1") (pintype "passive"))
    )
    (net (code "37") (name "Net-(IC1A-OUT)") (class "Default")
      (node (ref "D3") (pin "A") (pinfunction "A_A") (pintype "passive"))
      (node (ref "IC1") (pin "1") (pinfunction "OUT_1") (pintype "output"))
      (node (ref "R39") (pin "2") (pinfunction "2_2") (pintype "passive"))
    )
    (net (code "38") (name "Net-(IC1B--IN)") (class "Default")
      (node (ref "C6") (pin "2") (pinfunction "2_2") (pintype "passive"))
      (node (ref "IC1") (pin "6") (pinfunction "-IN_6") (pintype "input"))
      (node (ref "R11") (pin "2") (pinfunction "2_2") (pintype "passive"))
    )
    (net (code "39") (name "Net-(IC2A--IN)") (class "Default")
      (node (ref "C11") (pin "2") (pinfunction "2_2") (pintype "passive"))
      (node (ref "IC2") (pin "2") (pinfunction "-IN_2") (pintype "input"))
      (node (ref "R13") (pin "2") (pinfunction "2_2") (pintype "passive"))
      (node (ref "R14") (pin "1") (pinfunction "1_1") (pintype "passive"))
    )
    (net (code "40") (name "Net-(IC2B--IN)") (class "Default")
      (node (ref "IC2") (pin "6") (pinfunction "-IN_6") (pintype "input"))
      (node (ref "R19") (pin "2") (pinfunction "2_2") (pintype "passive"))
      (node (ref "R20") (pin "1") (pinfunction "1_1") (pintype "passive"))
    )
    (net (code "41") (name "Net-(IC3-3V3OUT)") (class "Default")
      (node (ref "C24") (pin "2") (pinfunction "2_2") (pintype "passive"))
      (node (ref "IC3") (pin "17") (pinfunction "3V3OUT_17") (pintype "output"))
    )
    (net (code "42") (name "Net-(IC3-OSCI)") (class "Default")
      (node (ref "IC3") (pin "27") (pinfunction "OSCI_27") (pintype "input"))
      (node (ref "IC3") (pin "28") (pinfunction "OSCO_28") (pintype "output"))
      (node (ref "R38") (pin "2") (pinfunction "2_2") (pintype "passive"))
    )
    (net (code "43") (name "Net-(IC3-USBDM)") (class "Default")
      (node (ref "IC3") (pin "16") (pinfunction "USBDM_16") (pintype "bidirectional"))
      (node (ref "X2") (pin "D-") (pinfunction "D-_D-") (pintype "bidirectional"))
    )
    (net (code "44") (name "Net-(IC3-USBDP)") (class "Default")
      (node (ref "IC3") (pin "15") (pinfunction "USBDP_15") (pintype "bidirectional"))
      (node (ref "X2") (pin "D+") (pinfunction "D+_D+") (pintype "bidirectional"))
    )
    (net (code "45") (name "Net-(IC3-~{DCD})") (class "Default")
      (node (ref "IC3") (pin "10") (pinfunction "~{DCD}_10") (pintype "input"))
      (node (ref "IC3") (pin "6") (pinfunction "~{RI}_6") (pintype "input"))
      (node (ref "IC3") (pin "9") (pinfunction "~{DSR}_9") (pintype "input"))
      (node (ref "R37") (pin "2") (pinfunction "2_2") (pintype "passive"))
    )
    (net (code "46") (name "Net-(IC4A--IN)") (class "Default")
      (node (ref "IC4") (pin "2") (pinfunction "-IN_2") (pintype "input"))
      (node (ref "R2") (pin "1") (pinfunction "1_1") (pintype "passive"))
      (node (ref "R3") (pin "2") (pinfunction "2_2") (pintype "passive"))
    )
    (net (code "47") (name "Net-(IC4A-OUT)") (class "Default")
      (node (ref "C2") (pin "1") (pinfunction "1_1") (pintype "passive"))
      (node (ref "C5") (pin "1") (pinfunction "1_1") (pintype "passive"))
      (node (ref "IC4") (pin "1") (pinfunction "OUT_1") (pintype "output"))
      (node (ref "R25") (pin "1") (pinfunction "E_1") (pintype "passive"))
    )
    (net (code "48") (name "Net-(IC4B--IN)") (class "Default")
      (node (ref "C36") (pin "2") (pinfunction "2_2") (pintype "passive"))
      (node (ref "IC4") (pin "6") (pinfunction "-IN_6") (pintype "input"))
      (node (ref "R23") (pin "1") (pinfunction "1_1") (pintype "passive"))
      (node (ref "R4") (pin "2") (pinfunction "2_2") (pintype "passive"))
    )
    (net (code "49") (name "Net-(IC4B-OUT)") (class "Default")
      (node (ref "C18") (pin "2") (pinfunction "2_2") (pintype "passive"))
      (node (ref "C36") (pin "1") (pinfunction "1_1") (pintype "passive"))
      (node (ref "IC4") (pin "7") (pinfunction "OUT_7") (pintype "output"))
      (node (ref "R24") (pin "1") (pinfunction "E_1") (pintype "passive"))
    )
    (net (code "50") (name "Net-(IC5-VI)") (class "Default")
      (node (ref "C9") (pin "2") (pinfunction "2_2") (pintype "passive"))
      (node (ref "F1") (pin "2") (pinfunction "2_2") (pintype "passive"))
      (node (ref "IC5") (pin "1") (pinfunction "VI_1") (pintype "input"))
    )
    (net (code "51") (name "Net-(IC6-DNU)") (class "Default")
      (node (ref "IC6") (pin "3") (pinfunction "DNU_3") (pintype "bidirectional"))
      (node (ref "R8") (pin "2") (pinfunction "2_2") (pintype "passive"))
    )
    (net (code "52") (name "Net-(IC6-HLD{slash})") (class "Default")
      (node (ref "IC6") (pin "7") (pinfunction "HLD/_7") (pintype "input"))
      (node (ref "R9") (pin "2") (pinfunction "2_2") (pintype "passive"))
    )
    (net (code "53") (name "Net-(LDR1-Pad1)") (class "Default")
      (node (ref "LDR1") (pin "1") (pinfunction "1_1") (pintype "passive"))
      (node (ref "R16") (pin "1") (pinfunction "1_1") (pintype "passive"))
      (node (ref "R17") (pin "2") (pinfunction "2_2") (pintype "passive"))
    )
    (net (code "54") (name "Net-(R24-A)") (class "Default")
      (node (ref "R23") (pin "2") (pinfunction "2_2") (pintype "passive"))
      (node (ref "R24") (pin "2") (pinfunction "S_2") (pintype "passive"))
      (node (ref "R24") (pin "3") (pinfunction "A_3") (pintype "passive"))
    )
    (net (code "55") (name "Net-(R25-A)") (class "Default")
      (node (ref "R25") (pin "2") (pinfunction "S_2") (pintype "passive"))
      (node (ref "R25") (pin "3") (pinfunction "A_3") (pintype "passive"))
      (node (ref "R3") (pin "1") (pinfunction "1_1") (pintype "passive"))
    )
    (net (code "56") (name "Net-(U1-AREF)") (class "Default")
      (node (ref "C33") (pin "2") (pinfunction "2_2") (pintype "passive"))
      (node (ref "U1") (pin "21") (pinfunction "AREF_21") (pintype "input"))
    )
    (net (code "57") (name "Net-(U1-PB0)") (class "Default")
      (node (ref "R41") (pin "2") (pinfunction "2_2") (pintype "passive"))
      (node (ref "U1") (pin "14") (pinfunction "PB0_14") (pintype "bidirectional"))
    )
    (net (code "58") (name "Net-(U1-PB1)") (class "Default")
      (node (ref "R42") (pin "2") (pinfunction "2_2") (pintype "passive"))
      (node (ref "U1") (pin "15") (pinfunction "PB1_15") (pintype "bidirectional"))
    )
    (net (code "59") (name "Net-(U1-PB2)") (class "Default")
      (node (ref "R43") (pin "2") (pinfunction "2_2") (pintype "passive"))
      (node (ref "U1") (pin "16") (pinfunction "PB2_16") (pintype "bidirectional"))
    )
    (net (code "60") (name "Net-(U1-PB7)") (class "Default")
      (node (ref "C21") (pin "2") (pinfunction "2_2") (pintype "passive"))
      (node (ref "Q1") (pin "1") (pinfunction "1_1") (pintype "passive"))
      (node (ref "U1") (pin "10") (pinfunction "PB7_10") (pintype "bidirectional"))
    )
    (net (code "61") (name "Net-(U1-PC4)") (class "Default")
      (node (ref "R44") (pin "1") (pinfunction "1_1") (pintype "passive"))
      (node (ref "U1") (pin "27") (pinfunction "PC4_27") (pintype "bidirectional"))
    )
    (net (code "62") (name "Net-(U1-PC5)") (class "Default")
      (node (ref "R45") (pin "1") (pinfunction "1_1") (pintype "passive"))
      (node (ref "U1") (pin "28") (pinfunction "PC5_28") (pintype "bidirectional"))
    )
    (net (code "63") (name "Net-(U1-PD0)") (class "Default")
      (node (ref "R26") (pin "2") (pinfunction "2_2") (pintype "passive"))
      (node (ref "U1") (pin "2") (pinfunction "PD0_2") (pintype "bidirectional"))
    )
    (net (code "64") (name "Net-(U1-PD1)") (class "Default")
      (node (ref "R40") (pin "2") (pinfunction "2_2") (pintype "passive"))
      (node (ref "U1") (pin "3") (pinfunction "PD1_3") (pintype "bidirectional"))
    )
    (net (code "65") (name "Net-(U1-PD5)") (class "Default")
      (node (ref "R27") (pin "2") (pinfunction "2_2") (pintype "passive"))
      (node (ref "U1") (pin "11") (pinfunction "PD5_11") (pintype "bidirectional"))
    )
    (net (code "66") (name "Net-(U1-PD6)") (class "Default")
      (node (ref "R28") (pin "2") (pinfunction "2_2") (pintype "passive"))
      (node (ref "U1") (pin "12") (pinfunction "PD6_12") (pintype "bidirectional"))
    )
    (net (code "67") (name "Net-(U2-VOUTA)") (class "Default")
      (node (ref "C4") (pin "2") (pinfunction "2_2") (pintype "passive"))
      (node (ref "U2") (pin "8") (pinfunction "VOUTA_8") (pintype "output"))
    )
    (net (code "68") (name "OSC") (class "Default")
      (node (ref "C20") (pin "2") (pinfunction "2_2") (pintype "passive"))
      (node (ref "Q1") (pin "2") (pinfunction "2_2") (pintype "passive"))
      (node (ref "U1") (pin "9") (pinfunction "PB6_9") (pintype "bidirectional"))
    )
    (net (code "69") (name "OUTPUT") (class "Default")
      (node (ref "J3") (pin "T") (pinfunction "T_T") (pintype "passive"))
      (node (ref "J3") (pin "TN") (pinfunction "TN_TN") (pintype "passive"))
      (node (ref "SV2") (pin "2") (pinfunction "2_2") (pintype "passive"))
    )
    (net (code "70") (name "PWM_DC") (class "Default")
      (node (ref "R34") (pin "1") (pinfunction "1_1") (pintype "passive"))
      (node (ref "U1") (pin "5") (pinfunction "PD3_5") (pintype "bidirectional"))
    )
    (net (code "71") (name "PWR_LED") (class "Default")
      (node (ref "D1") (pin "K") (pinfunction "C_K") (pintype "passive"))
      (node (ref "SV1") (pin "3") (pinfunction "3_3") (pintype "passive"))
    )
    (net (code "72") (name "RESET#") (class "Default")
      (node (ref "C37") (pin "2") (pinfunction "2_2") (pintype "passive"))
      (node (ref "IC3") (pin "19") (pinfunction "~{RESET}_19") (pintype "input"))
      (node (ref "R32") (pin "1") (pinfunction "1_1") (pintype "passive"))
      (node (ref "R33") (pin "2") (pinfunction "2_2") (pintype "passive"))
      (node (ref "SW2") (pin "P$2") (pinfunction "P$2_P$2") (pintype "passive"))
      (node (ref "U1") (pin "1") (pinfunction "PC6_1") (pintype "bidirectional"))
    )
    (net (code "73") (name "RTS#") (class "Default")
      (node (ref "IC3") (pin "3") (pinfunction "~{RTS}_3") (pintype "output"))
      (node (ref "R32") (pin "2") (pinfunction "2_2") (pintype "passive"))
    )
    (net (code "74") (name "RXD") (class "Default")
      (node (ref "IC3") (pin "5") (pinfunction "RXD_5") (pintype "input"))
      (node (ref "R26") (pin "1") (pinfunction "1_1") (pintype "passive"))
    )
    (net (code "75") (name "SPI_MISO") (class "Default")
      (node (ref "IC6") (pin "2") (pinfunction "SO_2") (pintype "output"))
      (node (ref "U1") (pin "18") (pinfunction "PB4_18") (pintype "bidirectional"))
    )
    (net (code "76") (name "SPI_MOSI") (class "Default")
      (node (ref "IC6") (pin "5") (pinfunction "SI_5") (pintype "input"))
      (node (ref "U1") (pin "17") (pinfunction "PB3_17") (pintype "bidirectional"))
      (node (ref "U2") (pin "4") (pinfunction "SDI_4") (pintype "input"))
    )
    (net (code "77") (name "SPI_SCK") (class "Default")
      (node (ref "IC6") (pin "6") (pinfunction "SCK_6") (pintype "input"))
      (node (ref "U1") (pin "19") (pinfunction "PB5_19") (pintype "bidirectional"))
      (node (ref "U2") (pin "3") (pinfunction "SCK_3") (pintype "input"))
    )
    (net (code "78") (name "TXD") (class "Default")
      (node (ref "IC3") (pin "1") (pinfunction "TXD_1") (pintype "output"))
      (node (ref "R40") (pin "1") (pinfunction "1_1") (pintype "passive"))
    )
    (net (code "79") (name "VCA_IN") (class "Default")
      (node (ref "C14") (pin "2") (pinfunction "2_2") (pintype "passive"))
      (node (ref "IC2") (pin "1") (pinfunction "OUT_1") (pintype "output"))
      (node (ref "LDR2") (pin "2") (pinfunction "2_2") (pintype "passive"))
      (node (ref "R14") (pin "2") (pinfunction "2_2") (pintype "passive"))
      (node (ref "R15") (pin "2") (pinfunction "2_2") (pintype "passive"))
    )
    (net (code "80") (name "VCA_OUT") (class "Default")
      (node (ref "C17") (pin "2") (pinfunction "2_2") (pintype "passive"))
      (node (ref "IC2") (pin "7") (pinfunction "OUT_7") (pintype "output"))
      (node (ref "R20") (pin "2") (pinfunction "2_2") (pintype "passive"))
    )
    (net (code "81") (name "VCC") (class "Default")
      (node (ref "C13") (pin "1") (pinfunction "1_1") (pintype "passive"))
      (node (ref "C25") (pin "2") (pinfunction "2_2") (pintype "passive"))
      (node (ref "C29") (pin "2") (pinfunction "2_2") (pintype "passive"))
      (node (ref "F1") (pin "1") (pinfunction "1_1") (pintype "passive"))
      (node (ref "IC2") (pin "8") (pinfunction "V+_8") (pintype "power_in"))
      (node (ref "IC4") (pin "8") (pinfunction "V+_8") (pintype "power_in"))
      (node (ref "J1") (pin "1") (pinfunction "1_1") (pintype "passive"))
      (node (ref "J1") (pin "2") (pinfunction "2_2") (pintype "passive"))
      (node (ref "R1") (pin "1") (pinfunction "1_1") (pintype "passive"))
      (node (ref "R35") (pin "2") (pinfunction "2_2") (pintype "passive"))
      (node (ref "R5") (pin "1") (pinfunction "1_1") (pintype "passive"))
    )
    (net (code "82") (name "VCCIO") (class "Default")
      (node (ref "IC3") (pin "4") (pinfunction "VCCIO_4") (pintype "power_in"))
      (node (ref "R30") (pin "1") (pinfunction "1_1") (pintype "passive"))
      (node (ref "R31") (pin "1") (pinfunction "1_1") (pintype "passive"))
    )
    (net (code "83") (name "VCF_IN") (class "Default")
      (node (ref "C10") (pin "2") (pinfunction "2_2") (pintype "passive"))
      (node (ref "C6") (pin "1") (pinfunction "1_1") (pintype "passive"))
      (node (ref "IC1") (pin "7") (pinfunction "OUT_7") (pintype "output"))
      (node (ref "R12") (pin "2") (pinfunction "2_2") (pintype "passive"))
    )
    (net (code "84") (name "V_BIAS") (class "Default")
      (node (ref "C3") (pin "2") (pinfunction "2_2") (pintype "passive"))
      (node (ref "C35") (pin "2") (pinfunction "2_2") (pintype "passive"))
      (node (ref "IC1") (pin "3") (pinfunction "+IN_3") (pintype "input"))
      (node (ref "IC1") (pin "5") (pinfunction "+IN_5") (pintype "input"))
      (node (ref "IC2") (pin "3") (pinfunction "+IN_3") (pintype "input"))
      (node (ref "IC2") (pin "5") (pinfunction "+IN_5") (pintype "input"))
      (node (ref "IC4") (pin "3") (pinfunction "+IN_3") (pintype "input"))
      (node (ref "IC4") (pin "5") (pinfunction "+IN_5") (pintype "input"))
      (node (ref "R5") (pin "2") (pinfunction "2_2") (pintype "passive"))
      (node (ref "R6") (pin "1") (pinfunction "1_1") (pintype "passive"))
    )
    (net (code "85") (name "unconnected-(IC3-CBUS0-Pad23)") (class "Default")
      (node (ref "IC3") (pin "23") (pinfunction "CBUS0_23") (pintype "bidirectional"))
    )
    (net (code "86") (name "unconnected-(IC3-CBUS3-Pad14)") (class "Default")
      (node (ref "IC3") (pin "14") (pinfunction "CBUS3_14") (pintype "bidirectional"))
    )
    (net (code "87") (name "unconnected-(IC3-CBUS4-Pad12)") (class "Default")
      (node (ref "IC3") (pin "12") (pinfunction "CBUS4_12") (pintype "bidirectional"))
    )
  )
)
